# idate.net
KiCad netlist of a schematic drawn in EAGLE
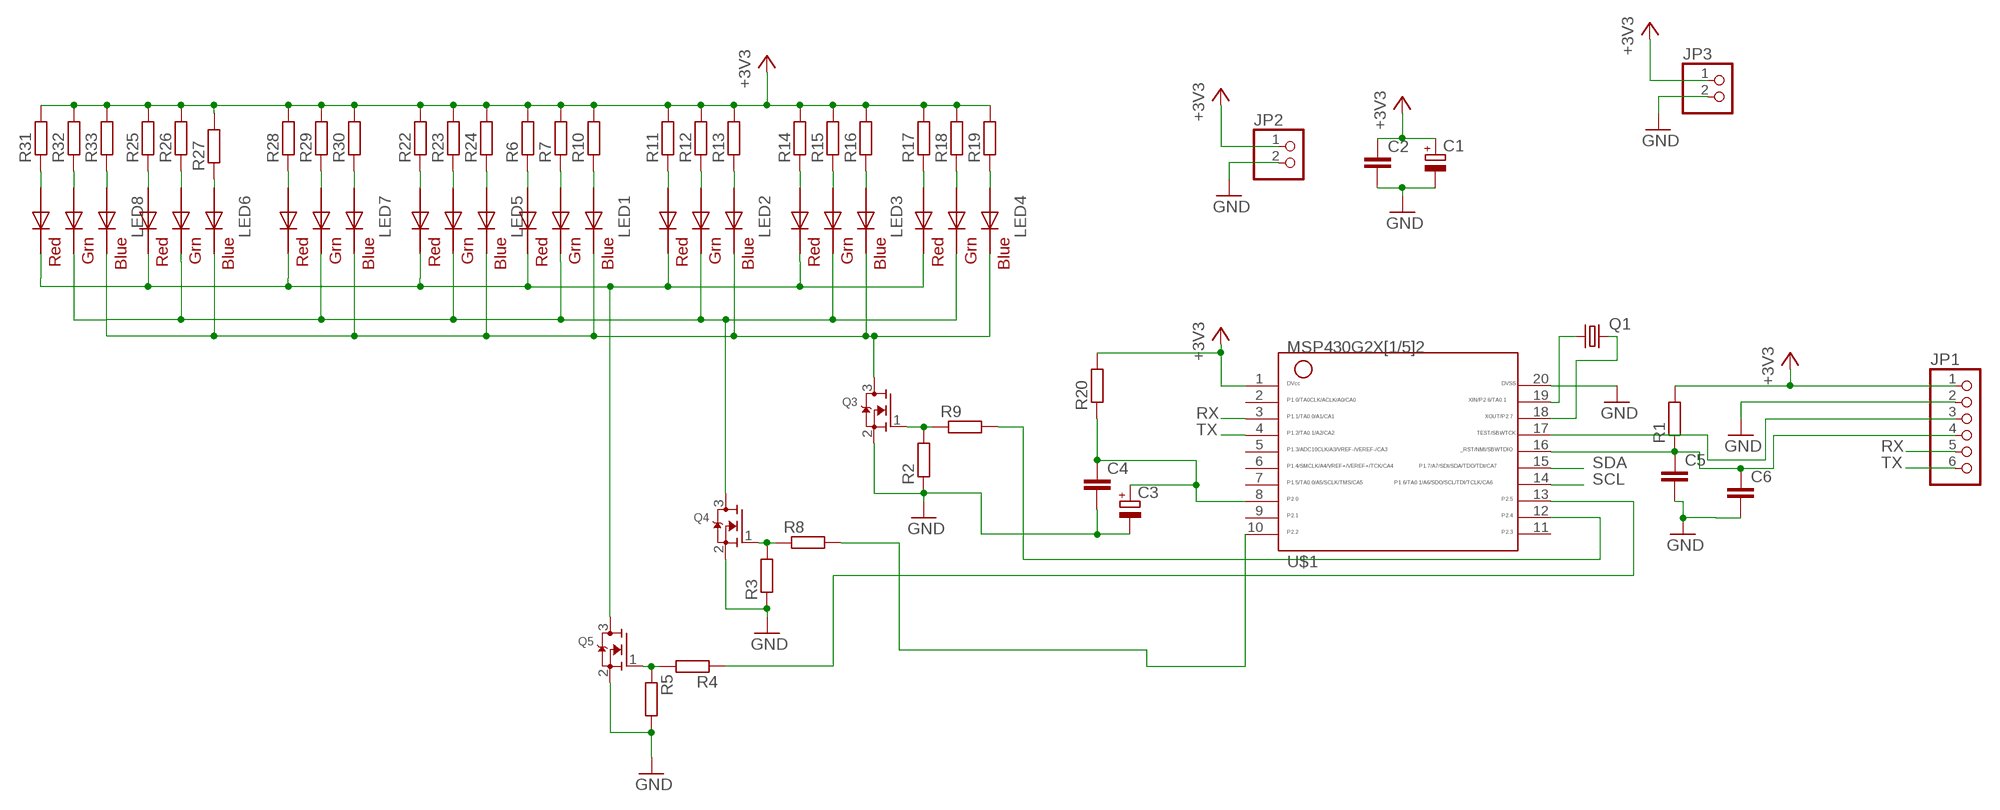
[diagram p0: schematic, sheet 1]

(export (version "E")
  (design (tool "Eeschema 10.0.6"))
  (components
    (comp (ref "C1")
      (value "CPOL-EUE5-8.5")
      (footprint "eagle-import:E5-8,5")
      (libsource (lib "eagle-import") (part "CPOL-EUE5-8.5"))
    )
    (comp (ref "C2")
      (value "C-EU025-030X050")
      (footprint "eagle-import:C025-030X050")
      (libsource (lib "eagle-import") (part "C-EU025-030X050"))
    )
    (comp (ref "C3")
      (value "CPOL-EUTT2D6L")
      (footprint "eagle-import:TT2D6L")
      (libsource (lib "eagle-import") (part "CPOL-EUTT2D6L"))
    )
    (comp (ref "C4")
      (value "C-EUC0603")
      (footprint "eagle-import:C0603")
      (libsource (lib "eagle-import") (part "C-EUC0603"))
    )
    (comp (ref "C5")
      (value "C-EU050-024X044")
      (footprint "eagle-import:C050-024X044")
      (libsource (lib "eagle-import") (part "C-EU050-024X044"))
    )
    (comp (ref "C6")
      (value "C-EUC0603")
      (footprint "eagle-import:C0603")
      (libsource (lib "eagle-import") (part "C-EUC0603"))
    )
    (comp (ref "JP1")
      (value "HEADER-1X6")
      (footprint "eagle-import:1X06_OVAL")
      (libsource (lib "eagle-import") (part "HEADER-1X6"))
    )
    (comp (ref "JP2")
      (value "HEADER-1X2")
      (footprint "eagle-import:1X02_OVAL")
      (libsource (lib "eagle-import") (part "HEADER-1X2"))
    )
    (comp (ref "JP3")
      (value "HEADER-1X2")
      (footprint "eagle-import:1X02_OVAL")
      (libsource (lib "eagle-import") (part "HEADER-1X2"))
    )
    (comp (ref "LED1")
      (value "RGBLED5050")
      (footprint "eagle-import:RGBLED5050")
      (libsource (lib "eagle-import") (part "RGBLED5050"))
    )
    (comp (ref "LED2")
      (value "RGBLED5050")
      (footprint "eagle-import:RGBLED5050")
      (libsource (lib "eagle-import") (part "RGBLED5050"))
    )
    (comp (ref "LED3")
      (value "RGBLED5050")
      (footprint "eagle-import:RGBLED5050")
      (libsource (lib "eagle-import") (part "RGBLED5050"))
    )
    (comp (ref "LED4")
      (value "RGBLED5050")
      (footprint "eagle-import:RGBLED5050")
      (libsource (lib "eagle-import") (part "RGBLED5050"))
    )
    (comp (ref "LED5")
      (value "RGBLED5050")
      (footprint "eagle-import:RGBLED5050")
      (libsource (lib "eagle-import") (part "RGBLED5050"))
    )
    (comp (ref "LED6")
      (value "RGBLED5050")
      (footprint "eagle-import:RGBLED5050")
      (libsource (lib "eagle-import") (part "RGBLED5050"))
    )
    (comp (ref "LED7")
      (value "RGBLED5050")
      (footprint "eagle-import:RGBLED5050")
      (libsource (lib "eagle-import") (part "RGBLED5050"))
    )
    (comp (ref "LED8")
      (value "RGBLED5050")
      (footprint "eagle-import:RGBLED5050")
      (libsource (lib "eagle-import") (part "RGBLED5050"))
    )
    (comp (ref "Q1")
      (value "CRYSTALTC26H")
      (footprint "eagle-import:TC26H")
      (libsource (lib "eagle-import") (part "CRYSTALTC26H"))
    )
    (comp (ref "Q3")
      (value "MOSFET-NREFLOW")
      (footprint "eagle-import:SOT23")
      (libsource (lib "eagle-import") (part "MOSFET-NREFLOW"))
    )
    (comp (ref "Q4")
      (value "MOSFET-NREFLOW")
      (footprint "eagle-import:SOT23")
      (libsource (lib "eagle-import") (part "MOSFET-NREFLOW"))
    )
    (comp (ref "Q5")
      (value "MOSFET-NREFLOW")
      (footprint "eagle-import:SOT23")
      (libsource (lib "eagle-import") (part "MOSFET-NREFLOW"))
    )
    (comp (ref "R1")
      (value "R-EU_0204/7")
      (footprint "eagle-import:0204_7")
      (libsource (lib "eagle-import") (part "R-EU_0204/7"))
    )
    (comp (ref "R2")
      (value "R-EU_0204/7")
      (footprint "eagle-import:0204_7")
      (libsource (lib "eagle-import") (part "R-EU_0204/7"))
    )
    (comp (ref "R3")
      (value "R-EU_0204/7")
      (footprint "eagle-import:0204_7")
      (libsource (lib "eagle-import") (part "R-EU_0204/7"))
    )
    (comp (ref "R4")
      (value "R-EU_0204/7")
      (footprint "eagle-import:0204_7")
      (libsource (lib "eagle-import") (part "R-EU_0204/7"))
    )
    (comp (ref "R5")
      (value "R-EU_0204/7")
      (footprint "eagle-import:0204_7")
      (libsource (lib "eagle-import") (part "R-EU_0204/7"))
    )
    (comp (ref "R6")
      (value "R-EU_0204/7")
      (footprint "eagle-import:0204_7")
      (libsource (lib "eagle-import") (part "R-EU_0204/7"))
    )
    (comp (ref "R7")
      (value "R-EU_0204/7")
      (footprint "eagle-import:0204_7")
      (libsource (lib "eagle-import") (part "R-EU_0204/7"))
    )
    (comp (ref "R8")
      (value "R-EU_0204/7")
      (footprint "eagle-import:0204_7")
      (libsource (lib "eagle-import") (part "R-EU_0204/7"))
    )
    (comp (ref "R9")
      (value "R-EU_0204/7")
      (footprint "eagle-import:0204_7")
      (libsource (lib "eagle-import") (part "R-EU_0204/7"))
    )
    (comp (ref "R10")
      (value "R-EU_0204/7")
      (footprint "eagle-import:0204_7")
      (libsource (lib "eagle-import") (part "R-EU_0204/7"))
    )
    (comp (ref "R11")
      (value "R-EU_0204/7")
      (footprint "eagle-import:0204_7")
      (libsource (lib "eagle-import") (part "R-EU_0204/7"))
    )
    (comp (ref "R12")
      (value "R-EU_0204/7")
      (footprint "eagle-import:0204_7")
      (libsource (lib "eagle-import") (part "R-EU_0204/7"))
    )
    (comp (ref "R13")
      (value "R-EU_0204/7")
      (footprint "eagle-import:0204_7")
      (libsource (lib "eagle-import") (part "R-EU_0204/7"))
    )
    (comp (ref "R14")
      (value "R-EU_0204/7")
      (footprint "eagle-import:0204_7")
      (libsource (lib "eagle-import") (part "R-EU_0204/7"))
    )
    (comp (ref "R15")
      (value "R-EU_0204/7")
      (footprint "eagle-import:0204_7")
      (libsource (lib "eagle-import") (part "R-EU_0204/7"))
    )
    (comp (ref "R16")
      (value "R-EU_0204/7")
      (footprint "eagle-import:0204_7")
      (libsource (lib "eagle-import") (part "R-EU_0204/7"))
    )
    (comp (ref "R17")
      (value "R-EU_0204/7")
      (footprint "eagle-import:0204_7")
      (libsource (lib "eagle-import") (part "R-EU_0204/7"))
    )
    (comp (ref "R18")
      (value "R-EU_0204/7")
      (footprint "eagle-import:0204_7")
      (libsource (lib "eagle-import") (part "R-EU_0204/7"))
    )
    (comp (ref "R19")
      (value "R-EU_0204/7")
      (footprint "eagle-import:0204_7")
      (libsource (lib "eagle-import") (part "R-EU_0204/7"))
    )
    (comp (ref "R20")
      (value "R-EU_0204/7")
      (footprint "eagle-import:0204_7")
      (libsource (lib "eagle-import") (part "R-EU_0204/7"))
    )
    (comp (ref "R22")
      (value "R-EU_0204/7")
      (footprint "eagle-import:0204_7")
      (libsource (lib "eagle-import") (part "R-EU_0204/7"))
    )
    (comp (ref "R23")
      (value "R-EU_0204/7")
      (footprint "eagle-import:0204_7")
      (libsource (lib "eagle-import") (part "R-EU_0204/7"))
    )
    (comp (ref "R24")
      (value "R-EU_0204/7")
      (footprint "eagle-import:0204_7")
      (libsource (lib "eagle-import") (part "R-EU_0204/7"))
    )
    (comp (ref "R25")
      (value "R-EU_0204/7")
      (footprint "eagle-import:0204_7")
      (libsource (lib "eagle-import") (part "R-EU_0204/7"))
    )
    (comp (ref "R26")
      (value "R-EU_0204/7")
      (footprint "eagle-import:0204_7")
      (libsource (lib "eagle-import") (part "R-EU_0204/7"))
    )
    (comp (ref "R27")
      (value "R-EU_0204/7")
      (footprint "eagle-import:0204_7")
      (libsource (lib "eagle-import") (part "R-EU_0204/7"))
    )
    (comp (ref "R28")
      (value "R-EU_0204/7")
      (footprint "eagle-import:0204_7")
      (libsource (lib "eagle-import") (part "R-EU_0204/7"))
    )
    (comp (ref "R29")
      (value "R-EU_0204/7")
      (footprint "eagle-import:0204_7")
      (libsource (lib "eagle-import") (part "R-EU_0204/7"))
    )
    (comp (ref "R30")
      (value "R-EU_0204/7")
      (footprint "eagle-import:0204_7")
      (libsource (lib "eagle-import") (part "R-EU_0204/7"))
    )
    (comp (ref "R31")
      (value "R-EU_0204/7")
      (footprint "eagle-import:0204_7")
      (libsource (lib "eagle-import") (part "R-EU_0204/7"))
    )
    (comp (ref "R32")
      (value "R-EU_0204/7")
      (footprint "eagle-import:0204_7")
      (libsource (lib "eagle-import") (part "R-EU_0204/7"))
    )
    (comp (ref "R33")
      (value "R-EU_0204/7")
      (footprint "eagle-import:0204_7")
      (libsource (lib "eagle-import") (part "R-EU_0204/7"))
    )
    (comp (ref "U$1")
      (value "G2X[1/5]2---N20")
      (footprint "eagle-import:N20")
      (libsource (lib "eagle-import") (part "G2X[1/5]2---N20"))
    )
  )
  (nets
    (net (code "1") (name "+3V3") (class "Default")
      (node (ref "C1") (pin "+") (pinfunction "+_+") (pintype "passive"))
      (node (ref "C2") (pin "1") (pinfunction "1_1") (pintype "passive"))
      (node (ref "JP1") (pin "1") (pinfunction "1_1") (pintype "passive"))
      (node (ref "JP2") (pin "1") (pinfunction "1_1") (pintype "passive"))
      (node (ref "JP3") (pin "1") (pinfunction "1_1") (pintype "passive"))
      (node (ref "R1") (pin "2") (pinfunction "2_2") (pintype "passive"))
      (node (ref "R10") (pin "2") (pinfunction "2_2") (pintype "passive"))
      (node (ref "R11") (pin "2") (pinfunction "2_2") (pintype "passive"))
      (node (ref "R12") (pin "2") (pinfunction "2_2") (pintype "passive"))
      (node (ref "R13") (pin "2") (pinfunction "2_2") (pintype "passive"))
      (node (ref "R14") (pin "2") (pinfunction "2_2") (pintype "passive"))
      (node (ref "R15") (pin "2") (pinfunction "2_2") (pintype "passive"))
      (node (ref "R16") (pin "2") (pinfunction "2_2") (pintype "passive"))
      (node (ref "R17") (pin "2") (pinfunction "2_2") (pintype "passive"))
      (node (ref "R18") (pin "2") (pinfunction "2_2") (pintype "passive"))
      (node (ref "R19") (pin "2") (pinfunction "2_2") (pintype "passive"))
      (node (ref "R20") (pin "2") (pinfunction "2_2") (pintype "passive"))
      (node (ref "R22") (pin "2") (pinfunction "2_2") (pintype "passive"))
      (node (ref "R23") (pin "2") (pinfunction "2_2") (pintype "passive"))
      (node (ref "R24") (pin "2") (pinfunction "2_2") (pintype "passive"))
      (node (ref "R25") (pin "2") (pinfunction "2_2") (pintype "passive"))
      (node (ref "R26") (pin "2") (pinfunction "2_2") (pintype "passive"))
      (node (ref "R27") (pin "2") (pinfunction "2_2") (pintype "passive"))
      (node (ref "R28") (pin "2") (pinfunction "2_2") (pintype "passive"))
      (node (ref "R29") (pin "2") (pinfunction "2_2") (pintype "passive"))
      (node (ref "R30") (pin "2") (pinfunction "2_2") (pintype "passive"))
      (node (ref "R31") (pin "2") (pinfunction "2_2") (pintype "passive"))
      (node (ref "R32") (pin "2") (pinfunction "2_2") (pintype "passive"))
      (node (ref "R33") (pin "2") (pinfunction "2_2") (pintype "passive"))
      (node (ref "R6") (pin "2") (pinfunction "2_2") (pintype "passive"))
      (node (ref "R7") (pin "2") (pinfunction "2_2") (pintype "passive"))
      (node (ref "U$1") (pin "1") (pinfunction "1_1") (pintype "bidirectional"))
    )
    (net (code "2") (name "GND") (class "Default")
      (node (ref "C1") (pin "-") (pinfunction "-_-") (pintype "passive"))
      (node (ref "C2") (pin "2") (pinfunction "2_2") (pintype "passive"))
      (node (ref "C3") (pin "-") (pinfunction "-_-") (pintype "passive"))
      (node (ref "C4") (pin "2") (pinfunction "2_2") (pintype "passive"))
      (node (ref "C5") (pin "2") (pinfunction "2_2") (pintype "passive"))
      (node (ref "C6") (pin "2") (pinfunction "2_2") (pintype "passive"))
      (node (ref "JP1") (pin "2") (pinfunction "2_2") (pintype "passive"))
      (node (ref "JP2") (pin "2") (pinfunction "2_2") (pintype "passive"))
      (node (ref "JP3") (pin "2") (pinfunction "2_2") (pintype "passive"))
      (node (ref "Q3") (pin "2") (pinfunction "S_2") (pintype "bidirectional"))
      (node (ref "Q4") (pin "2") (pinfunction "S_2") (pintype "bidirectional"))
      (node (ref "Q5") (pin "2") (pinfunction "S_2") (pintype "bidirectional"))
      (node (ref "R2") (pin "1") (pinfunction "1_1") (pintype "passive"))
      (node (ref "R3") (pin "1") (pinfunction "1_1") (pintype "passive"))
      (node (ref "R5") (pin "2") (pinfunction "2_2") (pintype "passive"))
      (node (ref "U$1") (pin "20") (pinfunction "20_20") (pintype "bidirectional"))
    )
    (net (code "3") (name "Net-(C3-Pad+)") (class "Default")
      (node (ref "C3") (pin "+") (pinfunction "+_+") (pintype "passive"))
      (node (ref "C4") (pin "1") (pinfunction "1_1") (pintype "passive"))
      (node (ref "R20") (pin "1") (pinfunction "1_1") (pintype "passive"))
      (node (ref "U$1") (pin "8") (pinfunction "8_8") (pintype "bidirectional"))
    )
    (net (code "4") (name "Net-(C5-Pad1)") (class "Default")
      (node (ref "C5") (pin "1") (pinfunction "1_1") (pintype "passive"))
      (node (ref "C6") (pin "1") (pinfunction "1_1") (pintype "passive"))
      (node (ref "JP1") (pin "4") (pinfunction "4_4") (pintype "passive"))
      (node (ref "R1") (pin "1") (pinfunction "1_1") (pintype "passive"))
      (node (ref "U$1") (pin "16") (pinfunction "16_16") (pintype "bidirectional"))
    )
    (net (code "5") (name "Net-(JP1-Pad3)") (class "Default")
      (node (ref "JP1") (pin "3") (pinfunction "3_3") (pintype "passive"))
      (node (ref "U$1") (pin "17") (pinfunction "17_17") (pintype "bidirectional"))
    )
    (net (code "6") (name "Net-(LED1-BLUE_A)") (class "Default")
      (node (ref "LED1") (pin "3") (pinfunction "BLUE_A_3") (pintype "bidirectional"))
      (node (ref "R10") (pin "1") (pinfunction "1_1") (pintype "passive"))
    )
    (net (code "7") (name "Net-(LED1-BLUE_C)") (class "Default")
      (node (ref "LED1") (pin "4") (pinfunction "BLUE_C_4") (pintype "bidirectional"))
      (node (ref "LED2") (pin "4") (pinfunction "BLUE_C_4") (pintype "bidirectional"))
      (node (ref "LED3") (pin "4") (pinfunction "BLUE_C_4") (pintype "bidirectional"))
      (node (ref "LED4") (pin "4") (pinfunction "BLUE_C_4") (pintype "bidirectional"))
      (node (ref "LED5") (pin "4") (pinfunction "BLUE_C_4") (pintype "bidirectional"))
      (node (ref "LED6") (pin "4") (pinfunction "BLUE_C_4") (pintype "bidirectional"))
      (node (ref "LED7") (pin "4") (pinfunction "BLUE_C_4") (pintype "bidirectional"))
      (node (ref "LED8") (pin "4") (pinfunction "BLUE_C_4") (pintype "bidirectional"))
      (node (ref "Q3") (pin "3") (pinfunction "D_3") (pintype "bidirectional"))
    )
    (net (code "8") (name "Net-(LED1-GREEN_A)") (class "Default")
      (node (ref "LED1") (pin "1") (pinfunction "GREEN_A_1") (pintype "bidirectional"))
      (node (ref "R7") (pin "1") (pinfunction "1_1") (pintype "passive"))
    )
    (net (code "9") (name "Net-(LED1-GREEN_C)") (class "Default")
      (node (ref "LED1") (pin "6") (pinfunction "GREEN_C_6") (pintype "bidirectional"))
      (node (ref "LED2") (pin "6") (pinfunction "GREEN_C_6") (pintype "bidirectional"))
      (node (ref "LED3") (pin "6") (pinfunction "GREEN_C_6") (pintype "bidirectional"))
      (node (ref "LED4") (pin "6") (pinfunction "GREEN_C_6") (pintype "bidirectional"))
      (node (ref "LED5") (pin "6") (pinfunction "GREEN_C_6") (pintype "bidirectional"))
      (node (ref "LED6") (pin "6") (pinfunction "GREEN_C_6") (pintype "bidirectional"))
      (node (ref "LED7") (pin "6") (pinfunction "GREEN_C_6") (pintype "bidirectional"))
      (node (ref "LED8") (pin "6") (pinfunction "GREEN_C_6") (pintype "bidirectional"))
      (node (ref "Q4") (pin "3") (pinfunction "D_3") (pintype "bidirectional"))
    )
    (net (code "10") (name "Net-(LED1-RED_A)") (class "Default")
      (node (ref "LED1") (pin "2") (pinfunction "RED_A_2") (pintype "bidirectional"))
      (node (ref "R6") (pin "1") (pinfunction "1_1") (pintype "passive"))
    )
    (net (code "11") (name "Net-(LED1-RED_C)") (class "Default")
      (node (ref "LED1") (pin "5") (pinfunction "RED_C_5") (pintype "bidirectional"))
      (node (ref "LED2") (pin "5") (pinfunction "RED_C_5") (pintype "bidirectional"))
      (node (ref "LED3") (pin "5") (pinfunction "RED_C_5") (pintype "bidirectional"))
      (node (ref "LED4") (pin "5") (pinfunction "RED_C_5") (pintype "bidirectional"))
      (node (ref "LED5") (pin "5") (pinfunction "RED_C_5") (pintype "bidirectional"))
      (node (ref "LED6") (pin "5") (pinfunction "RED_C_5") (pintype "bidirectional"))
      (node (ref "LED7") (pin "5") (pinfunction "RED_C_5") (pintype "bidirectional"))
      (node (ref "LED8") (pin "5") (pinfunction "RED_C_5") (pintype "bidirectional"))
      (node (ref "Q5") (pin "3") (pinfunction "D_3") (pintype "bidirectional"))
    )
    (net (code "12") (name "Net-(LED2-BLUE_A)") (class "Default")
      (node (ref "LED2") (pin "3") (pinfunction "BLUE_A_3") (pintype "bidirectional"))
      (node (ref "R13") (pin "1") (pinfunction "1_1") (pintype "passive"))
    )
    (net (code "13") (name "Net-(LED2-GREEN_A)") (class "Default")
      (node (ref "LED2") (pin "1") (pinfunction "GREEN_A_1") (pintype "bidirectional"))
      (node (ref "R12") (pin "1") (pinfunction "1_1") (pintype "passive"))
    )
    (net (code "14") (name "Net-(LED2-RED_A)") (class "Default")
      (node (ref "LED2") (pin "2") (pinfunction "RED_A_2") (pintype "bidirectional"))
      (node (ref "R11") (pin "1") (pinfunction "1_1") (pintype "passive"))
    )
    (net (code "15") (name "Net-(LED3-BLUE_A)") (class "Default")
      (node (ref "LED3") (pin "3") (pinfunction "BLUE_A_3") (pintype "bidirectional"))
      (node (ref "R16") (pin "1") (pinfunction "1_1") (pintype "passive"))
    )
    (net (code "16") (name "Net-(LED3-GREEN_A)") (class "Default")
      (node (ref "LED3") (pin "1") (pinfunction "GREEN_A_1") (pintype "bidirectional"))
      (node (ref "R15") (pin "1") (pinfunction "1_1") (pintype "passive"))
    )
    (net (code "17") (name "Net-(LED3-RED_A)") (class "Default")
      (node (ref "LED3") (pin "2") (pinfunction "RED_A_2") (pintype "bidirectional"))
      (node (ref "R14") (pin "1") (pinfunction "1_1") (pintype "passive"))
    )
    (net (code "18") (name "Net-(LED4-BLUE_A)") (class "Default")
      (node (ref "LED4") (pin "3") (pinfunction "BLUE_A_3") (pintype "bidirectional"))
      (node (ref "R19") (pin "1") (pinfunction "1_1") (pintype "passive"))
    )
    (net (code "19") (name "Net-(LED4-GREEN_A)") (class "Default")
      (node (ref "LED4") (pin "1") (pinfunction "GREEN_A_1") (pintype "bidirectional"))
      (node (ref "R18") (pin "1") (pinfunction "1_1") (pintype "passive"))
    )
    (net (code "20") (name "Net-(LED4-RED_A)") (class "Default")
      (node (ref "LED4") (pin "2") (pinfunction "RED_A_2") (pintype "bidirectional"))
      (node (ref "R17") (pin "1") (pinfunction "1_1") (pintype "passive"))
    )
    (net (code "21") (name "Net-(LED5-BLUE_A)") (class "Default")
      (node (ref "LED5") (pin "3") (pinfunction "BLUE_A_3") (pintype "bidirectional"))
      (node (ref "R24") (pin "1") (pinfunction "1_1") (pintype "passive"))
    )
    (net (code "22") (name "Net-(LED5-GREEN_A)") (class "Default")
      (node (ref "LED5") (pin "1") (pinfunction "GREEN_A_1") (pintype "bidirectional"))
      (node (ref "R23") (pin "1") (pinfunction "1_1") (pintype "passive"))
    )
    (net (code "23") (name "Net-(LED5-RED_A)") (class "Default")
      (node (ref "LED5") (pin "2") (pinfunction "RED_A_2") (pintype "bidirectional"))
      (node (ref "R22") (pin "1") (pinfunction "1_1") (pintype "passive"))
    )
    (net (code "24") (name "Net-(LED6-BLUE_A)") (class "Default")
      (node (ref "LED6") (pin "3") (pinfunction "BLUE_A_3") (pintype "bidirectional"))
      (node (ref "R27") (pin "1") (pinfunction "1_1") (pintype "passive"))
    )
    (net (code "25") (name "Net-(LED6-GREEN_A)") (class "Default")
      (node (ref "LED6") (pin "1") (pinfunction "GREEN_A_1") (pintype "bidirectional"))
      (node (ref "R26") (pin "1") (pinfunction "1_1") (pintype "passive"))
    )
    (net (code "26") (name "Net-(LED6-RED_A)") (class "Default")
      (node (ref "LED6") (pin "2") (pinfunction "RED_A_2") (pintype "bidirectional"))
      (node (ref "R25") (pin "1") (pinfunction "1_1") (pintype "passive"))
    )
    (net (code "27") (name "Net-(LED7-BLUE_A)") (class "Default")
      (node (ref "LED7") (pin "3") (pinfunction "BLUE_A_3") (pintype "bidirectional"))
      (node (ref "R30") (pin "1") (pinfunction "1_1") (pintype "passive"))
    )
    (net (code "28") (name "Net-(LED7-GREEN_A)") (class "Default")
      (node (ref "LED7") (pin "1") (pinfunction "GREEN_A_1") (pintype "bidirectional"))
      (node (ref "R29") (pin "1") (pinfunction "1_1") (pintype "passive"))
    )
    (net (code "29") (name "Net-(LED7-RED_A)") (class "Default")
      (node (ref "LED7") (pin "2") (pinfunction "RED_A_2") (pintype "bidirectional"))
      (node (ref "R28") (pin "1") (pinfunction "1_1") (pintype "passive"))
    )
    (net (code "30") (name "Net-(LED8-BLUE_A)") (class "Default")
      (node (ref "LED8") (pin "3") (pinfunction "BLUE_A_3") (pintype "bidirectional"))
      (node (ref "R33") (pin "1") (pinfunction "1_1") (pintype "passive"))
    )
    (net (code "31") (name "Net-(LED8-GREEN_A)") (class "Default")
      (node (ref "LED8") (pin "1") (pinfunction "GREEN_A_1") (pintype "bidirectional"))
      (node (ref "R32") (pin "1") (pinfunction "1_1") (pintype "passive"))
    )
    (net (code "32") (name "Net-(LED8-RED_A)") (class "Default")
      (node (ref "LED8") (pin "2") (pinfunction "RED_A_2") (pintype "bidirectional"))
      (node (ref "R31") (pin "1") (pinfunction "1_1") (pintype "passive"))
    )
    (net (code "33") (name "Net-(Q1-Pad1)") (class "Default")
      (node (ref "Q1") (pin "1") (pinfunction "1_1") (pintype "passive"))
      (node (ref "U$1") (pin "19") (pinfunction "19_19") (pintype "bidirectional"))
    )
    (net (code "34") (name "Net-(Q1-Pad2)") (class "Default")
      (node (ref "Q1") (pin "2") (pinfunction "2_2") (pintype "passive"))
      (node (ref "U$1") (pin "18") (pinfunction "18_18") (pintype "bidirectional"))
    )
    (net (code "35") (name "Net-(Q3-G)") (class "Default")
      (node (ref "Q3") (pin "1") (pinfunction "G_1") (pintype "bidirectional"))
      (node (ref "R2") (pin "2") (pinfunction "2_2") (pintype "passive"))
      (node (ref "R9") (pin "1") (pinfunction "1_1") (pintype "passive"))
    )
    (net (code "36") (name "Net-(Q4-G)") (class "Default")
      (node (ref "Q4") (pin "1") (pinfunction "G_1") (pintype "bidirectional"))
      (node (ref "R3") (pin "2") (pinfunction "2_2") (pintype "passive"))
      (node (ref "R8") (pin "1") (pinfunction "1_1") (pintype "passive"))
    )
    (net (code "37") (name "Net-(Q5-G)") (class "Default")
      (node (ref "Q5") (pin "1") (pinfunction "G_1") (pintype "bidirectional"))
      (node (ref "R4") (pin "2") (pinfunction "2_2") (pintype "passive"))
      (node (ref "R5") (pin "1") (pinfunction "1_1") (pintype "passive"))
    )
    (net (code "38") (name "Net-(R4-Pad1)") (class "Default")
      (node (ref "R4") (pin "1") (pinfunction "1_1") (pintype "passive"))
      (node (ref "U$1") (pin "13") (pinfunction "13_13") (pintype "bidirectional"))
    )
    (net (code "39") (name "Net-(R8-Pad2)") (class "Default")
      (node (ref "R8") (pin "2") (pinfunction "2_2") (pintype "passive"))
      (node (ref "U$1") (pin "10") (pinfunction "10_10") (pintype "bidirectional"))
    )
    (net (code "40") (name "Net-(R9-Pad2)") (class "Default")
      (node (ref "R9") (pin "2") (pinfunction "2_2") (pintype "passive"))
      (node (ref "U$1") (pin "12") (pinfunction "12_12") (pintype "bidirectional"))
    )
    (net (code "41") (name "RX") (class "Default")
      (node (ref "JP1") (pin "5") (pinfunction "5_5") (pintype "passive"))
      (node (ref "U$1") (pin "3") (pinfunction "3_3") (pintype "bidirectional"))
    )
    (net (code "42") (name "SCL") (class "Default")
      (node (ref "U$1") (pin "14") (pinfunction "14_14") (pintype "bidirectional"))
    )
    (net (code "43") (name "SDA") (class "Default")
      (node (ref "U$1") (pin "15") (pinfunction "15_15") (pintype "bidirectional"))
    )
    (net (code "44") (name "TX") (class "Default")
      (node (ref "JP1") (pin "6") (pinfunction "6_6") (pintype "passive"))
      (node (ref "U$1") (pin "4") (pinfunction "4_4") (pintype "bidirectional"))
    )
    (net (code "45") (name "unconnected-(U$1-Pad2)") (class "Default")
      (node (ref "U$1") (pin "2") (pinfunction "2_2") (pintype "bidirectional"))
    )
    (net (code "46") (name "unconnected-(U$1-Pad5)") (class "Default")
      (node (ref "U$1") (pin "5") (pinfunction "5_5") (pintype "bidirectional"))
    )
    (net (code "47") (name "unconnected-(U$1-Pad6)") (class "Default")
      (node (ref "U$1") (pin "6") (pinfunction "6_6") (pintype "bidirectional"))
    )
    (net (code "48") (name "unconnected-(U$1-Pad7)") (class "Default")
      (node (ref "U$1") (pin "7") (pinfunction "7_7") (pintype "bidirectional"))
    )
    (net (code "49") (name "unconnected-(U$1-Pad9)") (class "Default")
      (node (ref "U$1") (pin "9") (pinfunction "9_9") (pintype "bidirectional"))
    )
    (net (code "50") (name "unconnected-(U$1-Pad11)") (class "Default")
      (node (ref "U$1") (pin "11") (pinfunction "11_11") (pintype "bidirectional"))
    )
  )
)
